# OSSC_HDMI_Audio_v1_3_A3.net
KiCad netlist of a schematic drawn in EAGLE
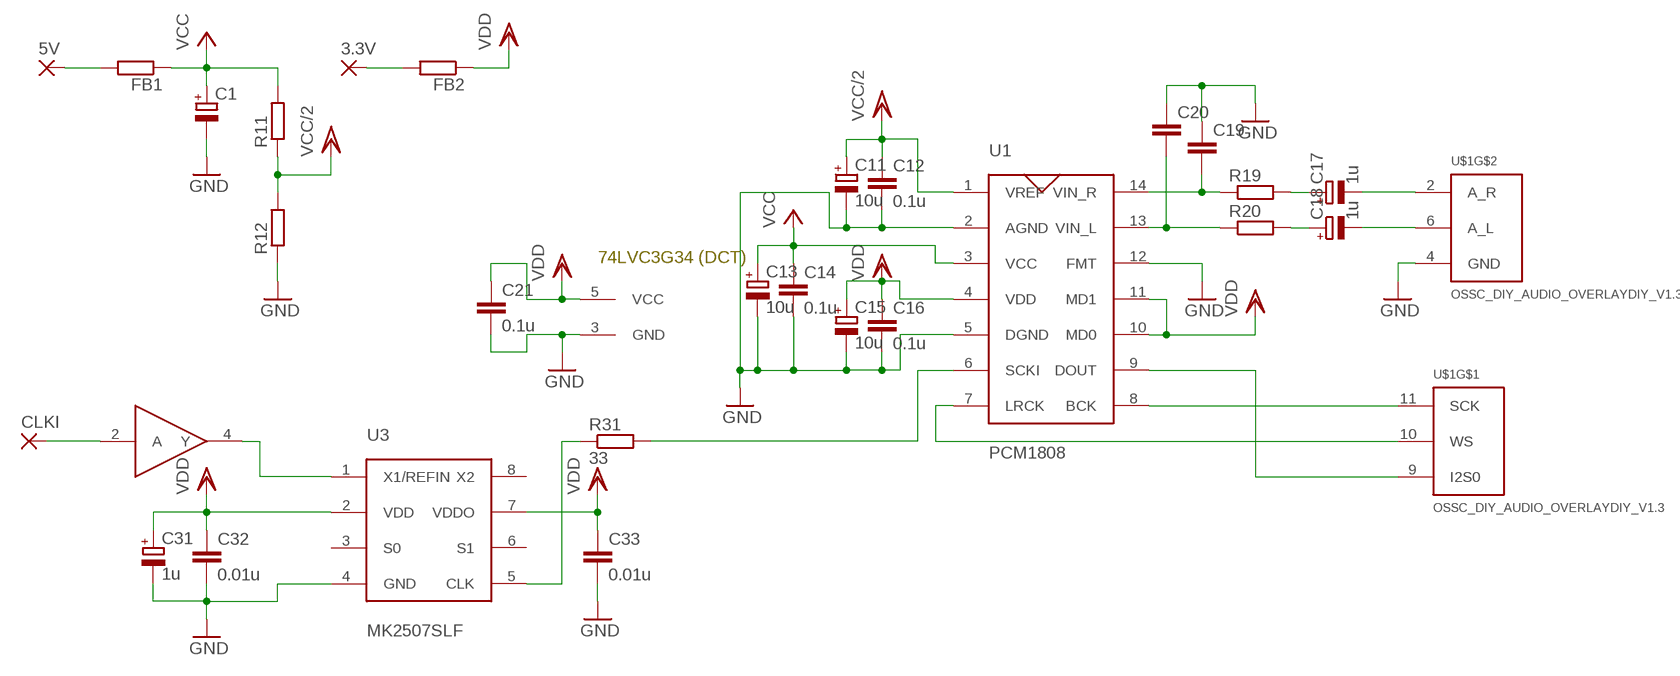
[diagram p0: schematic, sheet 1]

(export (version "E")
  (design (tool "Eeschema 10.0.6"))
  (components
    (comp (ref "3.3V")
      (value "SMD2")
      (footprint "eagle-import:SMD1,27-2,54")
      (libsource (lib "eagle-import") (part "SMD2"))
    )
    (comp (ref "5V")
      (value "SMD2")
      (footprint "eagle-import:SMD1,27-2,54")
      (libsource (lib "eagle-import") (part "SMD2"))
    )
    (comp (ref "C1")
      (value "CPOL-EUSMCC")
      (footprint "eagle-import:SMC_C")
      (libsource (lib "eagle-import") (part "CPOL-EUSMCC"))
    )
    (comp (ref "C11")
      (value "10u")
      (footprint "eagle-import:SMC_A")
      (libsource (lib "eagle-import") (part "CPOL-EUSMCA"))
    )
    (comp (ref "C12")
      (value "0.1u")
      (footprint "eagle-import:C0603")
      (libsource (lib "eagle-import") (part "C-EUC0603"))
    )
    (comp (ref "C13")
      (value "10u")
      (footprint "eagle-import:SMC_A")
      (libsource (lib "eagle-import") (part "CPOL-EUSMCA"))
    )
    (comp (ref "C14")
      (value "0.1u")
      (footprint "eagle-import:C0603")
      (libsource (lib "eagle-import") (part "C-EUC0603"))
    )
    (comp (ref "C15")
      (value "10u")
      (footprint "eagle-import:SMC_A")
      (libsource (lib "eagle-import") (part "CPOL-EUSMCA"))
    )
    (comp (ref "C16")
      (value "0.1u")
      (footprint "eagle-import:C0603")
      (libsource (lib "eagle-import") (part "C-EUC0603"))
    )
    (comp (ref "C17")
      (value "1u")
      (footprint "eagle-import:SMC_A")
      (libsource (lib "eagle-import") (part "CPOL-EUSMCA"))
    )
    (comp (ref "C18")
      (value "1u")
      (footprint "eagle-import:SMC_A")
      (libsource (lib "eagle-import") (part "CPOL-EUSMCA"))
    )
    (comp (ref "C19")
      (value "C-EUC0603")
      (footprint "eagle-import:C0603")
      (libsource (lib "eagle-import") (part "C-EUC0603"))
    )
    (comp (ref "C20")
      (value "C-EUC0603")
      (footprint "eagle-import:C0603")
      (libsource (lib "eagle-import") (part "C-EUC0603"))
    )
    (comp (ref "C21")
      (value "0.1u")
      (footprint "eagle-import:C0603")
      (libsource (lib "eagle-import") (part "C-EUC0603"))
    )
    (comp (ref "C31")
      (value "1u")
      (footprint "eagle-import:SMC_A")
      (libsource (lib "eagle-import") (part "CPOL-EUSMCA"))
    )
    (comp (ref "C32")
      (value "0.01u")
      (footprint "eagle-import:C0603")
      (libsource (lib "eagle-import") (part "C-EUC0603"))
    )
    (comp (ref "C33")
      (value "0.01u")
      (footprint "eagle-import:C0603")
      (libsource (lib "eagle-import") (part "C-EUC0603"))
    )
    (comp (ref "CLKI")
      (value "SMD2")
      (footprint "eagle-import:SMD1,27-2,54")
      (libsource (lib "eagle-import") (part "SMD2"))
    )
    (comp (ref "FB1")
      (value "R-EU_R0603")
      (footprint "eagle-import:R0603")
      (libsource (lib "eagle-import") (part "R-EU_R0603"))
    )
    (comp (ref "FB2")
      (value "R-EU_R0603")
      (footprint "eagle-import:R0603")
      (libsource (lib "eagle-import") (part "R-EU_R0603"))
    )
    (comp (ref "R11")
      (value "R-EU_R0603")
      (footprint "eagle-import:R0603")
      (libsource (lib "eagle-import") (part "R-EU_R0603"))
    )
    (comp (ref "R12")
      (value "R-EU_R0603")
      (footprint "eagle-import:R0603")
      (libsource (lib "eagle-import") (part "R-EU_R0603"))
    )
    (comp (ref "R19")
      (value "R-EU_R0603")
      (footprint "eagle-import:R0603")
      (libsource (lib "eagle-import") (part "R-EU_R0603"))
    )
    (comp (ref "R20")
      (value "R-EU_R0603")
      (footprint "eagle-import:R0603")
      (libsource (lib "eagle-import") (part "R-EU_R0603"))
    )
    (comp (ref "R31")
      (value "33")
      (footprint "eagle-import:R0603")
      (libsource (lib "eagle-import") (part "R-EU_R0603"))
    )
    (comp (ref "U$1")
      (value "OSSC_DIY_AUDIO_OVERLAYDIY_V1.3")
      (footprint "eagle-import:OSSC_OVERLAY_V1.3")
      (libsource (lib "eagle-import") (part "OSSC_DIY_AUDIO_OVERLAYDIY_V1.3"))
    )
    (comp (ref "U1")
      (value "PCM1808")
      (footprint "eagle-import:PCM1808")
      (libsource (lib "eagle-import") (part "PCM1808"))
    )
    (comp (ref "U2")
      (value "74LVC1G34")
      (footprint "eagle-import:74LVC1G34DCK")
      (libsource (lib "eagle-import") (part "74LVC1G34"))
    )
    (comp (ref "U3")
      (value "MK2507SLF")
      (footprint "eagle-import:SOIC8")
      (libsource (lib "eagle-import") (part "MK2507SLF"))
    )
  )
  (nets
    (net (code "1") (name "GND") (class "Default")
      (node (ref "C1") (pin "-") (pinfunction "-_-") (pintype "passive"))
      (node (ref "C11") (pin "-") (pinfunction "-_-") (pintype "passive"))
      (node (ref "C12") (pin "2") (pinfunction "2_2") (pintype "passive"))
      (node (ref "C13") (pin "-") (pinfunction "-_-") (pintype "passive"))
      (node (ref "C14") (pin "2") (pinfunction "2_2") (pintype "passive"))
      (node (ref "C15") (pin "-") (pinfunction "-_-") (pintype "passive"))
      (node (ref "C16") (pin "2") (pinfunction "2_2") (pintype "passive"))
      (node (ref "C19") (pin "1") (pinfunction "1_1") (pintype "passive"))
      (node (ref "C20") (pin "1") (pinfunction "1_1") (pintype "passive"))
      (node (ref "C21") (pin "2") (pinfunction "2_2") (pintype "passive"))
      (node (ref "C31") (pin "-") (pinfunction "-_-") (pintype "passive"))
      (node (ref "C32") (pin "2") (pinfunction "2_2") (pintype "passive"))
      (node (ref "C33") (pin "2") (pinfunction "2_2") (pintype "passive"))
      (node (ref "R12") (pin "1") (pinfunction "1_1") (pintype "passive"))
      (node (ref "U$1") (pin "4") (pinfunction "GND_4") (pintype "bidirectional"))
      (node (ref "U1") (pin "12") (pinfunction "FMT_12") (pintype "bidirectional"))
      (node (ref "U1") (pin "2") (pinfunction "AGND_2") (pintype "bidirectional"))
      (node (ref "U1") (pin "5") (pinfunction "DGND_5") (pintype "bidirectional"))
      (node (ref "U2") (pin "3") (pinfunction "GND_3") (pintype "bidirectional"))
      (node (ref "U3") (pin "4") (pinfunction "GND_4") (pintype "bidirectional"))
    )
    (net (code "2") (name "Net-(3.3V-P)") (class "Default")
      (node (ref "3.3V") (pin "1") (pinfunction "P_1") (pintype "passive"))
      (node (ref "FB2") (pin "2") (pinfunction "2_2") (pintype "passive"))
    )
    (net (code "3") (name "Net-(5V-P)") (class "Default")
      (node (ref "5V") (pin "1") (pinfunction "P_1") (pintype "passive"))
      (node (ref "FB1") (pin "2") (pinfunction "2_2") (pintype "passive"))
    )
    (net (code "4") (name "Net-(C17-Pad+)") (class "Default")
      (node (ref "C17") (pin "+") (pinfunction "+_+") (pintype "passive"))
      (node (ref "R19") (pin "2") (pinfunction "2_2") (pintype "passive"))
    )
    (net (code "5") (name "Net-(C18-Pad+)") (class "Default")
      (node (ref "C18") (pin "+") (pinfunction "+_+") (pintype "passive"))
      (node (ref "R20") (pin "2") (pinfunction "2_2") (pintype "passive"))
    )
    (net (code "6") (name "Net-(CLKI-P)") (class "Default")
      (node (ref "CLKI") (pin "1") (pinfunction "P_1") (pintype "passive"))
      (node (ref "U2") (pin "2") (pinfunction "A_2") (pintype "bidirectional"))
    )
    (net (code "7") (name "Net-(U$1A-I2S0)") (class "Default")
      (node (ref "U$1") (pin "9") (pinfunction "I2S0_9") (pintype "bidirectional"))
      (node (ref "U1") (pin "9") (pinfunction "DOUT_9") (pintype "bidirectional"))
    )
    (net (code "8") (name "Net-(U$1A-SCK)") (class "Default")
      (node (ref "U$1") (pin "11") (pinfunction "SCK_11") (pintype "bidirectional"))
      (node (ref "U1") (pin "8") (pinfunction "BCK_8") (pintype "bidirectional"))
    )
    (net (code "9") (name "Net-(U$1A-WS)") (class "Default")
      (node (ref "U$1") (pin "10") (pinfunction "WS_10") (pintype "bidirectional"))
      (node (ref "U1") (pin "7") (pinfunction "LRCK_7") (pintype "bidirectional"))
    )
    (net (code "10") (name "Net-(U$1B-A_L)") (class "Default")
      (node (ref "C18") (pin "-") (pinfunction "-_-") (pintype "passive"))
      (node (ref "U$1") (pin "6") (pinfunction "A_L_6") (pintype "bidirectional"))
    )
    (net (code "11") (name "Net-(U$1B-A_R)") (class "Default")
      (node (ref "C17") (pin "-") (pinfunction "-_-") (pintype "passive"))
      (node (ref "U$1") (pin "2") (pinfunction "A_R_2") (pintype "bidirectional"))
    )
    (net (code "12") (name "Net-(U1-SCKI)") (class "Default")
      (node (ref "R31") (pin "2") (pinfunction "2_2") (pintype "passive"))
      (node (ref "U1") (pin "6") (pinfunction "SCKI_6") (pintype "bidirectional"))
    )
    (net (code "13") (name "Net-(U1-VIN_L)") (class "Default")
      (node (ref "C20") (pin "2") (pinfunction "2_2") (pintype "passive"))
      (node (ref "R20") (pin "1") (pinfunction "1_1") (pintype "passive"))
      (node (ref "U1") (pin "13") (pinfunction "VIN_L_13") (pintype "bidirectional"))
    )
    (net (code "14") (name "Net-(U1-VIN_R)") (class "Default")
      (node (ref "C19") (pin "2") (pinfunction "2_2") (pintype "passive"))
      (node (ref "R19") (pin "1") (pinfunction "1_1") (pintype "passive"))
      (node (ref "U1") (pin "14") (pinfunction "VIN_R_14") (pintype "bidirectional"))
    )
    (net (code "15") (name "Net-(U2A-Y)") (class "Default")
      (node (ref "U2") (pin "4") (pinfunction "Y_4") (pintype "bidirectional"))
      (node (ref "U3") (pin "1") (pinfunction "X1/REFIN_1") (pintype "bidirectional"))
    )
    (net (code "16") (name "Net-(U3-CLK)") (class "Default")
      (node (ref "R31") (pin "1") (pinfunction "1_1") (pintype "passive"))
      (node (ref "U3") (pin "5") (pinfunction "CLK_5") (pintype "bidirectional"))
    )
    (net (code "17") (name "VCC") (class "Default")
      (node (ref "C1") (pin "+") (pinfunction "+_+") (pintype "passive"))
      (node (ref "C13") (pin "+") (pinfunction "+_+") (pintype "passive"))
      (node (ref "C14") (pin "1") (pinfunction "1_1") (pintype "passive"))
      (node (ref "FB1") (pin "1") (pinfunction "1_1") (pintype "passive"))
      (node (ref "R11") (pin "2") (pinfunction "2_2") (pintype "passive"))
      (node (ref "U1") (pin "3") (pinfunction "VCC_3") (pintype "bidirectional"))
    )
    (net (code "18") (name "VCC{slash}2") (class "Default")
      (node (ref "C11") (pin "+") (pinfunction "+_+") (pintype "passive"))
      (node (ref "C12") (pin "1") (pinfunction "1_1") (pintype "passive"))
      (node (ref "R11") (pin "1") (pinfunction "1_1") (pintype "passive"))
      (node (ref "R12") (pin "2") (pinfunction "2_2") (pintype "passive"))
      (node (ref "U1") (pin "1") (pinfunction "VREF_1") (pintype "bidirectional"))
    )
    (net (code "19") (name "VDD") (class "Default")
      (node (ref "C15") (pin "+") (pinfunction "+_+") (pintype "passive"))
      (node (ref "C16") (pin "1") (pinfunction "1_1") (pintype "passive"))
      (node (ref "C21") (pin "1") (pinfunction "1_1") (pintype "passive"))
      (node (ref "C31") (pin "+") (pinfunction "+_+") (pintype "passive"))
      (node (ref "C32") (pin "1") (pinfunction "1_1") (pintype "passive"))
      (node (ref "C33") (pin "1") (pinfunction "1_1") (pintype "passive"))
      (node (ref "FB2") (pin "1") (pinfunction "1_1") (pintype "passive"))
      (node (ref "U1") (pin "10") (pinfunction "MD0_10") (pintype "bidirectional"))
      (node (ref "U1") (pin "11") (pinfunction "MD1_11") (pintype "bidirectional"))
      (node (ref "U1") (pin "4") (pinfunction "VDD_4") (pintype "bidirectional"))
      (node (ref "U2") (pin "5") (pinfunction "VCC_5") (pintype "bidirectional"))
      (node (ref "U3") (pin "2") (pinfunction "VDD_2") (pintype "bidirectional"))
      (node (ref "U3") (pin "7") (pinfunction "VDDO_7") (pintype "bidirectional"))
    )
    (net (code "20") (name "unconnected-(U3-S0-Pad3)") (class "Default")
      (node (ref "U3") (pin "3") (pinfunction "S0_3") (pintype "bidirectional"))
    )
    (net (code "21") (name "unconnected-(U3-S1-Pad6)") (class "Default")
      (node (ref "U3") (pin "6") (pinfunction "S1_6") (pintype "bidirectional"))
    )
    (net (code "22") (name "unconnected-(U3-X2-Pad8)") (class "Default")
      (node (ref "U3") (pin "8") (pinfunction "X2_8") (pintype "bidirectional"))
    )
  )
)
